# M204D.net
KiCad netlist of a schematic drawn in EAGLE
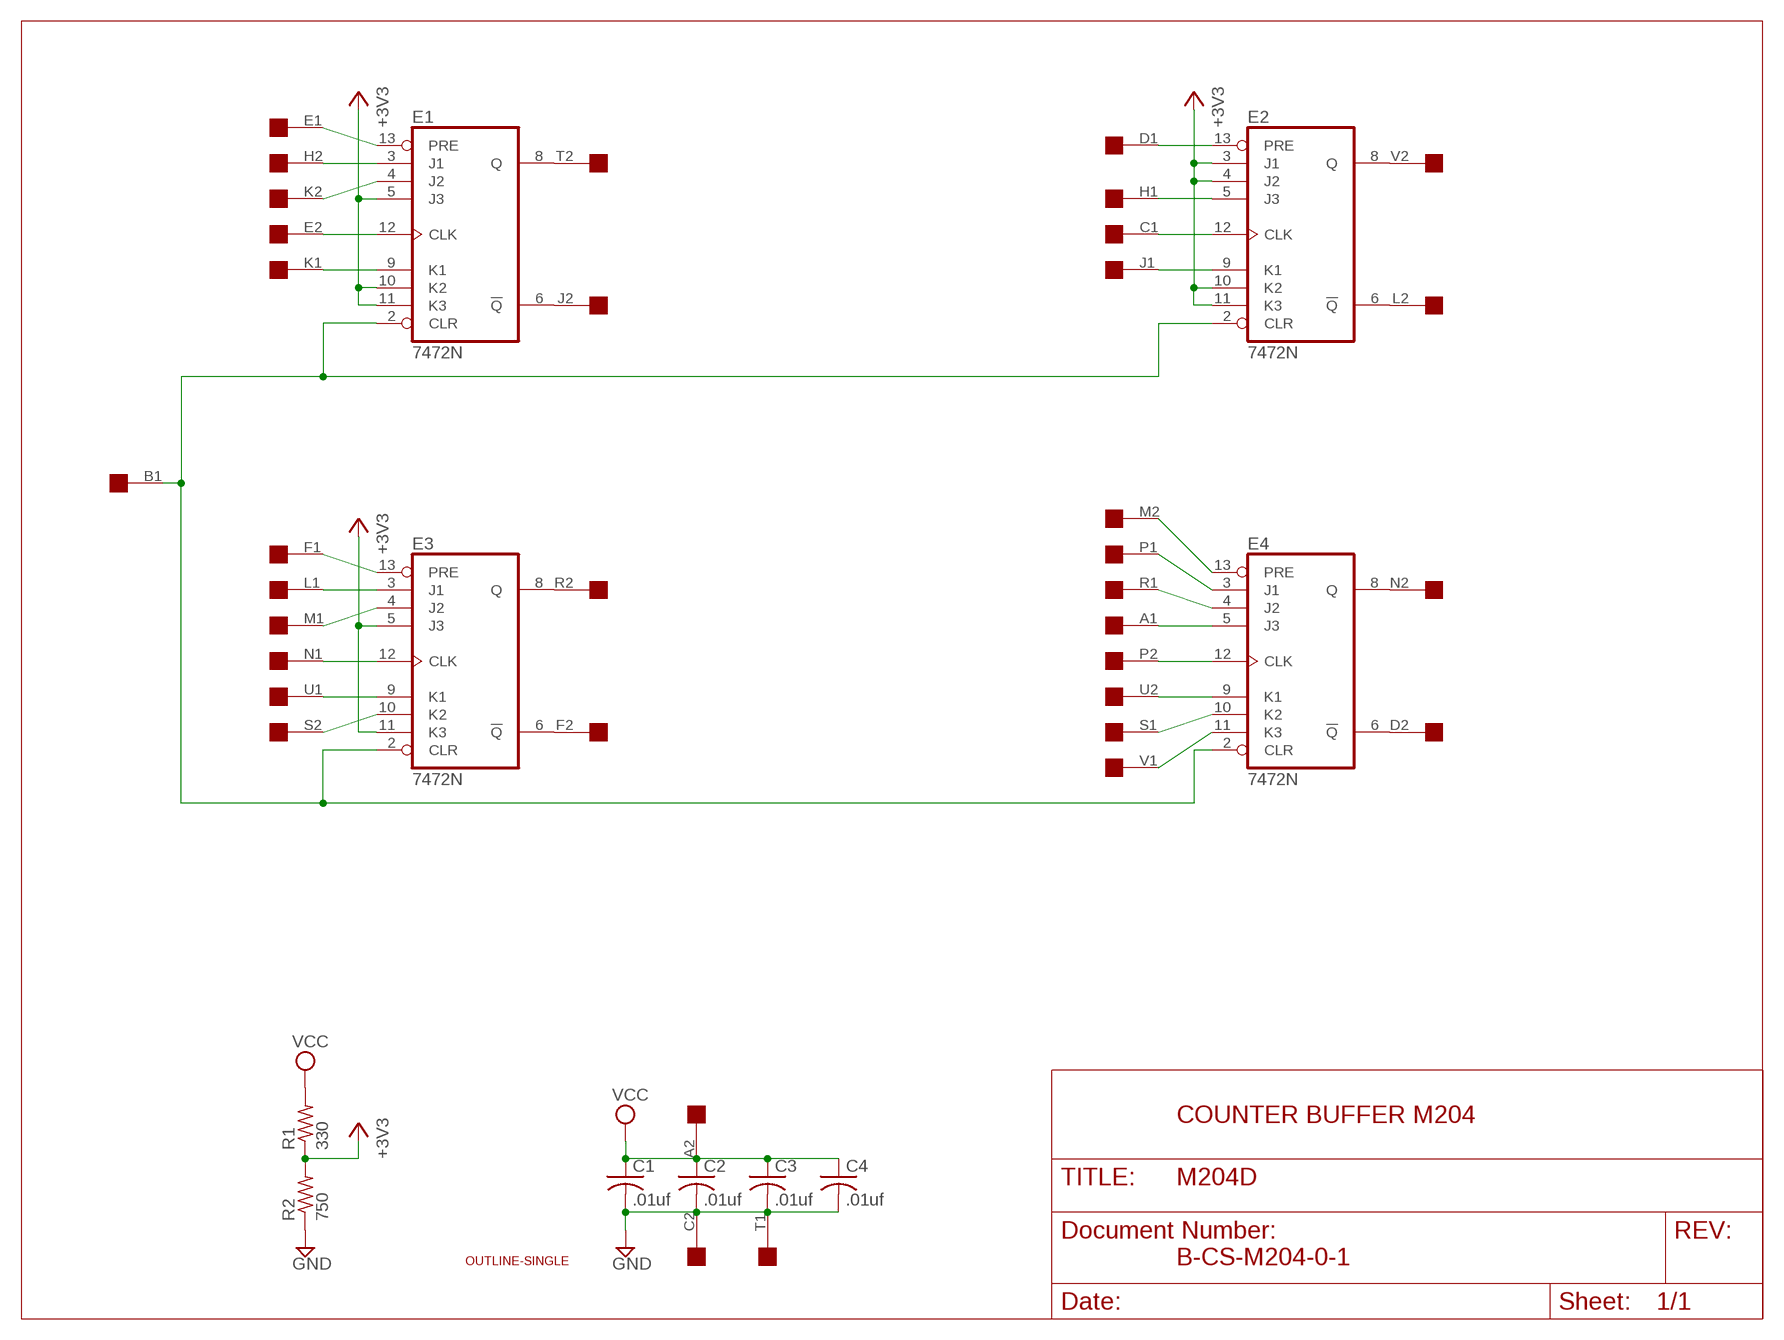
[diagram p0: schematic, sheet 1]

(export (version "E")
  (design (tool "Eeschema 10.0.6"))
  (components
    (comp (ref "C1")
      (value ".01uf")
      (footprint "eagle-import:C050-025X075")
      (libsource (lib "eagle-import") (part "C-US050-025X075"))
    )
    (comp (ref "C2")
      (value ".01uf")
      (footprint "eagle-import:C050-025X075")
      (libsource (lib "eagle-import") (part "C-US050-025X075"))
    )
    (comp (ref "C3")
      (value ".01uf")
      (footprint "eagle-import:C050-025X075")
      (libsource (lib "eagle-import") (part "C-US050-025X075"))
    )
    (comp (ref "C4")
      (value ".01uf")
      (footprint "eagle-import:C050-025X075")
      (libsource (lib "eagle-import") (part "C-US050-025X075"))
    )
    (comp (ref "E1")
      (value "7472N")
      (footprint "eagle-import:DIL14")
      (libsource (lib "eagle-import") (part "7472N"))
    )
    (comp (ref "E2")
      (value "7472N")
      (footprint "eagle-import:DIL14")
      (libsource (lib "eagle-import") (part "7472N"))
    )
    (comp (ref "E3")
      (value "7472N")
      (footprint "eagle-import:DIL14")
      (libsource (lib "eagle-import") (part "7472N"))
    )
    (comp (ref "E4")
      (value "7472N")
      (footprint "eagle-import:DIL14")
      (libsource (lib "eagle-import") (part "7472N"))
    )
    (comp (ref "R1")
      (value "330")
      (footprint "eagle-import:0207_10")
      (libsource (lib "eagle-import") (part "R-US_0207/10"))
    )
    (comp (ref "R2")
      (value "750")
      (footprint "eagle-import:0207_10")
      (libsource (lib "eagle-import") (part "R-US_0207/10"))
    )
    (comp (ref "U$1")
      (value "OUTLINE-SINGLE")
      (footprint "eagle-import:SINGLE")
      (libsource (lib "eagle-import") (part "OUTLINE-SINGLE"))
    )
    (comp (ref "U$2")
      (value "EDGE-2CONNECTOR")
      (footprint "eagle-import:EDGE-CON2")
      (libsource (lib "eagle-import") (part "EDGE-2CONNECTOR"))
    )
  )
  (nets
    (net (code "1") (name "+3V3") (class "Default")
      (node (ref "E1") (pin "10") (pinfunction "K2_10") (pintype "input"))
      (node (ref "E1") (pin "11") (pinfunction "K3_11") (pintype "input"))
      (node (ref "E1") (pin "5") (pinfunction "J3_5") (pintype "input"))
      (node (ref "E2") (pin "10") (pinfunction "K2_10") (pintype "input"))
      (node (ref "E2") (pin "11") (pinfunction "K3_11") (pintype "input"))
      (node (ref "E2") (pin "3") (pinfunction "J1_3") (pintype "input"))
      (node (ref "E2") (pin "4") (pinfunction "J2_4") (pintype "input"))
      (node (ref "E3") (pin "11") (pinfunction "K3_11") (pintype "input"))
      (node (ref "E3") (pin "5") (pinfunction "J3_5") (pintype "input"))
      (node (ref "R1") (pin "1") (pinfunction "1_1") (pintype "passive"))
      (node (ref "R2") (pin "2") (pinfunction "2_2") (pintype "passive"))
    )
    (net (code "2") (name "GND") (class "Default")
      (node (ref "C1") (pin "2") (pinfunction "2_2") (pintype "passive"))
      (node (ref "C2") (pin "2") (pinfunction "2_2") (pintype "passive"))
      (node (ref "C3") (pin "2") (pinfunction "2_2") (pintype "passive"))
      (node (ref "C4") (pin "2") (pinfunction "2_2") (pintype "passive"))
      (node (ref "R2") (pin "1") (pinfunction "1_1") (pintype "passive"))
      (node (ref "U$2") (pin "C2") (pinfunction "1_C2") (pintype "bidirectional"))
      (node (ref "U$2") (pin "T1") (pinfunction "1_T1") (pintype "bidirectional"))
    )
    (net (code "3") (name "Net-(E1A-CLK)") (class "Default")
      (node (ref "E1") (pin "12") (pinfunction "CLK_12") (pintype "input"))
      (node (ref "U$2") (pin "E2") (pinfunction "1_E2") (pintype "bidirectional"))
    )
    (net (code "4") (name "Net-(E1A-CLR)") (class "Default")
      (node (ref "E1") (pin "2") (pinfunction "CLR_2") (pintype "input"))
      (node (ref "E2") (pin "2") (pinfunction "CLR_2") (pintype "input"))
      (node (ref "E3") (pin "2") (pinfunction "CLR_2") (pintype "input"))
      (node (ref "E4") (pin "2") (pinfunction "CLR_2") (pintype "input"))
      (node (ref "U$2") (pin "B1") (pinfunction "1_B1") (pintype "bidirectional"))
    )
    (net (code "5") (name "Net-(E1A-J1)") (class "Default")
      (node (ref "E1") (pin "3") (pinfunction "J1_3") (pintype "input"))
      (node (ref "U$2") (pin "H2") (pinfunction "1_H2") (pintype "bidirectional"))
    )
    (net (code "6") (name "Net-(E1A-J2)") (class "Default")
      (node (ref "E1") (pin "4") (pinfunction "J2_4") (pintype "input"))
      (node (ref "U$2") (pin "K2") (pinfunction "1_K2") (pintype "bidirectional"))
    )
    (net (code "7") (name "Net-(E1A-K1)") (class "Default")
      (node (ref "E1") (pin "9") (pinfunction "K1_9") (pintype "input"))
      (node (ref "U$2") (pin "K1") (pinfunction "1_K1") (pintype "bidirectional"))
    )
    (net (code "8") (name "Net-(E1A-PRE)") (class "Default")
      (node (ref "E1") (pin "13") (pinfunction "PRE_13") (pintype "input"))
      (node (ref "U$2") (pin "E1") (pinfunction "1_E1") (pintype "bidirectional"))
    )
    (net (code "9") (name "Net-(E1A-Q)") (class "Default")
      (node (ref "E1") (pin "8") (pinfunction "Q_8") (pintype "output"))
      (node (ref "U$2") (pin "T2") (pinfunction "1_T2") (pintype "bidirectional"))
    )
    (net (code "10") (name "Net-(E1A-~{Q})") (class "Default")
      (node (ref "E1") (pin "6") (pinfunction "~{Q}_6") (pintype "output"))
      (node (ref "U$2") (pin "J2") (pinfunction "1_J2") (pintype "bidirectional"))
    )
    (net (code "11") (name "Net-(E2A-CLK)") (class "Default")
      (node (ref "E2") (pin "12") (pinfunction "CLK_12") (pintype "input"))
      (node (ref "U$2") (pin "C1") (pinfunction "1_C1") (pintype "bidirectional"))
    )
    (net (code "12") (name "Net-(E2A-J3)") (class "Default")
      (node (ref "E2") (pin "5") (pinfunction "J3_5") (pintype "input"))
      (node (ref "U$2") (pin "H1") (pinfunction "1_H1") (pintype "bidirectional"))
    )
    (net (code "13") (name "Net-(E2A-K1)") (class "Default")
      (node (ref "E2") (pin "9") (pinfunction "K1_9") (pintype "input"))
      (node (ref "U$2") (pin "J1") (pinfunction "1_J1") (pintype "bidirectional"))
    )
    (net (code "14") (name "Net-(E2A-PRE)") (class "Default")
      (node (ref "E2") (pin "13") (pinfunction "PRE_13") (pintype "input"))
      (node (ref "U$2") (pin "D1") (pinfunction "1_D1") (pintype "bidirectional"))
    )
    (net (code "15") (name "Net-(E2A-Q)") (class "Default")
      (node (ref "E2") (pin "8") (pinfunction "Q_8") (pintype "output"))
      (node (ref "U$2") (pin "V2") (pinfunction "1_V2") (pintype "bidirectional"))
    )
    (net (code "16") (name "Net-(E2A-~{Q})") (class "Default")
      (node (ref "E2") (pin "6") (pinfunction "~{Q}_6") (pintype "output"))
      (node (ref "U$2") (pin "L2") (pinfunction "1_L2") (pintype "bidirectional"))
    )
    (net (code "17") (name "Net-(E3A-CLK)") (class "Default")
      (node (ref "E3") (pin "12") (pinfunction "CLK_12") (pintype "input"))
      (node (ref "U$2") (pin "N1") (pinfunction "1_N1") (pintype "bidirectional"))
    )
    (net (code "18") (name "Net-(E3A-J1)") (class "Default")
      (node (ref "E3") (pin "3") (pinfunction "J1_3") (pintype "input"))
      (node (ref "U$2") (pin "L1") (pinfunction "1_L1") (pintype "bidirectional"))
    )
    (net (code "19") (name "Net-(E3A-J2)") (class "Default")
      (node (ref "E3") (pin "4") (pinfunction "J2_4") (pintype "input"))
      (node (ref "U$2") (pin "M1") (pinfunction "1_M1") (pintype "bidirectional"))
    )
    (net (code "20") (name "Net-(E3A-K1)") (class "Default")
      (node (ref "E3") (pin "9") (pinfunction "K1_9") (pintype "input"))
      (node (ref "U$2") (pin "U1") (pinfunction "1_U1") (pintype "bidirectional"))
    )
    (net (code "21") (name "Net-(E3A-K2)") (class "Default")
      (node (ref "E3") (pin "10") (pinfunction "K2_10") (pintype "input"))
      (node (ref "U$2") (pin "S2") (pinfunction "1_S2") (pintype "bidirectional"))
    )
    (net (code "22") (name "Net-(E3A-PRE)") (class "Default")
      (node (ref "E3") (pin "13") (pinfunction "PRE_13") (pintype "input"))
      (node (ref "U$2") (pin "F1") (pinfunction "1_F1") (pintype "bidirectional"))
    )
    (net (code "23") (name "Net-(E3A-Q)") (class "Default")
      (node (ref "E3") (pin "8") (pinfunction "Q_8") (pintype "output"))
      (node (ref "U$2") (pin "R2") (pinfunction "1_R2") (pintype "bidirectional"))
    )
    (net (code "24") (name "Net-(E3A-~{Q})") (class "Default")
      (node (ref "E3") (pin "6") (pinfunction "~{Q}_6") (pintype "output"))
      (node (ref "U$2") (pin "F2") (pinfunction "1_F2") (pintype "bidirectional"))
    )
    (net (code "25") (name "Net-(E4A-CLK)") (class "Default")
      (node (ref "E4") (pin "12") (pinfunction "CLK_12") (pintype "input"))
      (node (ref "U$2") (pin "P2") (pinfunction "1_P2") (pintype "bidirectional"))
    )
    (net (code "26") (name "Net-(E4A-J1)") (class "Default")
      (node (ref "E4") (pin "3") (pinfunction "J1_3") (pintype "input"))
      (node (ref "U$2") (pin "P1") (pinfunction "1_P1") (pintype "bidirectional"))
    )
    (net (code "27") (name "Net-(E4A-J2)") (class "Default")
      (node (ref "E4") (pin "4") (pinfunction "J2_4") (pintype "input"))
      (node (ref "U$2") (pin "R1") (pinfunction "1_R1") (pintype "bidirectional"))
    )
    (net (code "28") (name "Net-(E4A-J3)") (class "Default")
      (node (ref "E4") (pin "5") (pinfunction "J3_5") (pintype "input"))
      (node (ref "U$2") (pin "A1") (pinfunction "1_A1") (pintype "bidirectional"))
    )
    (net (code "29") (name "Net-(E4A-K1)") (class "Default")
      (node (ref "E4") (pin "9") (pinfunction "K1_9") (pintype "input"))
      (node (ref "U$2") (pin "U2") (pinfunction "1_U2") (pintype "bidirectional"))
    )
    (net (code "30") (name "Net-(E4A-K2)") (class "Default")
      (node (ref "E4") (pin "10") (pinfunction "K2_10") (pintype "input"))
      (node (ref "U$2") (pin "S1") (pinfunction "1_S1") (pintype "bidirectional"))
    )
    (net (code "31") (name "Net-(E4A-K3)") (class "Default")
      (node (ref "E4") (pin "11") (pinfunction "K3_11") (pintype "input"))
      (node (ref "U$2") (pin "V1") (pinfunction "1_V1") (pintype "bidirectional"))
    )
    (net (code "32") (name "Net-(E4A-PRE)") (class "Default")
      (node (ref "E4") (pin "13") (pinfunction "PRE_13") (pintype "input"))
      (node (ref "U$2") (pin "M2") (pinfunction "1_M2") (pintype "bidirectional"))
    )
    (net (code "33") (name "Net-(E4A-Q)") (class "Default")
      (node (ref "E4") (pin "8") (pinfunction "Q_8") (pintype "output"))
      (node (ref "U$2") (pin "N2") (pinfunction "1_N2") (pintype "bidirectional"))
    )
    (net (code "34") (name "Net-(E4A-~{Q})") (class "Default")
      (node (ref "E4") (pin "6") (pinfunction "~{Q}_6") (pintype "output"))
      (node (ref "U$2") (pin "D2") (pinfunction "1_D2") (pintype "bidirectional"))
    )
    (net (code "35") (name "VCC") (class "Default")
      (node (ref "C1") (pin "1") (pinfunction "1_1") (pintype "passive"))
      (node (ref "C2") (pin "1") (pinfunction "1_1") (pintype "passive"))
      (node (ref "C3") (pin "1") (pinfunction "1_1") (pintype "passive"))
      (node (ref "C4") (pin "1") (pinfunction "1_1") (pintype "passive"))
      (node (ref "R1") (pin "2") (pinfunction "2_2") (pintype "passive"))
      (node (ref "U$2") (pin "A2") (pinfunction "1_A2") (pintype "bidirectional"))
    )
  )
)
